# encoder.net
KiCad netlist of a schematic drawn in EAGLE
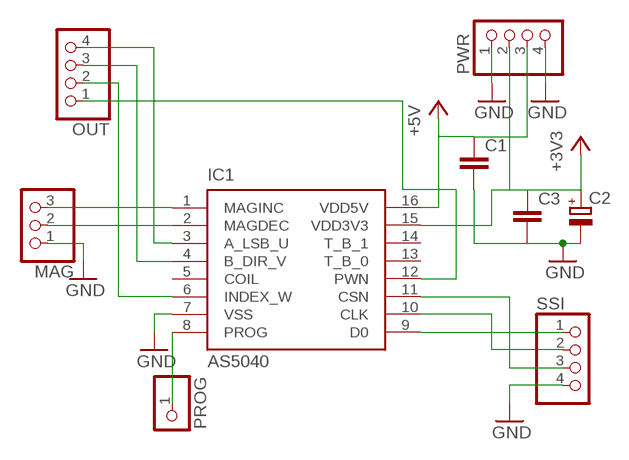
[diagram p0: schematic, sheet 1]

(export (version "E")
  (design (tool "Eeschema 10.0.6"))
  (components
    (comp (ref "C1")
      (value "C-EUC0805")
      (footprint "eagle-import:C0805")
      (libsource (lib "eagle-import") (part "C-EUC0805"))
    )
    (comp (ref "C2")
      (value "CPOL-EUE2,5-6E")
      (footprint "eagle-import:E2,5-6E")
      (libsource (lib "eagle-import") (part "CPOL-EUE2,5-6E"))
    )
    (comp (ref "C3")
      (value "C-EUC0805")
      (footprint "eagle-import:C0805")
      (libsource (lib "eagle-import") (part "C-EUC0805"))
    )
    (comp (ref "IC1")
      (value "AS5040")
      (footprint "eagle-import:SSOP16")
      (fields (field (name "MPN") "AS5040ASSU"))
      (libsource (lib "eagle-import") (part "AS5040"))
    )
    (comp (ref "MAG")
      (value "PINHD-1X3")
      (footprint "eagle-import:1X03")
      (libsource (lib "eagle-import") (part "PINHD-1X3"))
    )
    (comp (ref "OUT")
      (value "PINHD-1X4")
      (footprint "eagle-import:1X04")
      (libsource (lib "eagle-import") (part "PINHD-1X4"))
    )
    (comp (ref "PROG")
      (value "PINHD-1X1")
      (footprint "eagle-import:1X01")
      (libsource (lib "eagle-import") (part "PINHD-1X1"))
    )
    (comp (ref "PWR")
      (value "PINHD-1X4")
      (footprint "eagle-import:1X04")
      (libsource (lib "eagle-import") (part "PINHD-1X4"))
    )
    (comp (ref "SSI")
      (value "PINHD-1X4")
      (footprint "eagle-import:1X04")
      (libsource (lib "eagle-import") (part "PINHD-1X4"))
    )
  )
  (nets
    (net (code "1") (name "+3V3") (class "Default")
      (node (ref "C2") (pin "+") (pinfunction "+_+") (pintype "passive"))
      (node (ref "C3") (pin "1") (pinfunction "1_1") (pintype "passive"))
      (node (ref "IC1") (pin "15") (pinfunction "VDD3V3_15") (pintype "passive"))
      (node (ref "PWR") (pin "2") (pinfunction "2_2") (pintype "passive"))
    )
    (net (code "2") (name "+5V") (class "Default")
      (node (ref "C1") (pin "1") (pinfunction "1_1") (pintype "passive"))
      (node (ref "IC1") (pin "16") (pinfunction "VDD5V_16") (pintype "passive"))
      (node (ref "PWR") (pin "3") (pinfunction "3_3") (pintype "passive"))
    )
    (net (code "3") (name "GND") (class "Default")
      (node (ref "C1") (pin "2") (pinfunction "2_2") (pintype "passive"))
      (node (ref "C2") (pin "-") (pinfunction "-_-") (pintype "passive"))
      (node (ref "C3") (pin "2") (pinfunction "2_2") (pintype "passive"))
      (node (ref "IC1") (pin "7") (pinfunction "VSS_7") (pintype "passive"))
      (node (ref "MAG") (pin "1") (pinfunction "1_1") (pintype "passive"))
      (node (ref "PWR") (pin "1") (pinfunction "1_1") (pintype "passive"))
      (node (ref "PWR") (pin "4") (pinfunction "4_4") (pintype "passive"))
      (node (ref "SSI") (pin "4") (pinfunction "4_4") (pintype "passive"))
    )
    (net (code "4") (name "Net-(IC1-A_LSB_U)") (class "Default")
      (node (ref "IC1") (pin "3") (pinfunction "A_LSB_U_3") (pintype "output"))
      (node (ref "OUT") (pin "4") (pinfunction "4_4") (pintype "passive"))
    )
    (net (code "5") (name "Net-(IC1-B_DIR_V)") (class "Default")
      (node (ref "IC1") (pin "4") (pinfunction "B_DIR_V_4") (pintype "output"))
      (node (ref "OUT") (pin "3") (pinfunction "3_3") (pintype "passive"))
    )
    (net (code "6") (name "Net-(IC1-CLK)") (class "Default")
      (node (ref "IC1") (pin "10") (pinfunction "CLK_10") (pintype "input"))
      (node (ref "SSI") (pin "2") (pinfunction "2_2") (pintype "passive"))
    )
    (net (code "7") (name "Net-(IC1-CSN)") (class "Default")
      (node (ref "IC1") (pin "11") (pinfunction "CSN_11") (pintype "input"))
      (node (ref "SSI") (pin "3") (pinfunction "3_3") (pintype "passive"))
    )
    (net (code "8") (name "Net-(IC1-D0)") (class "Default")
      (node (ref "IC1") (pin "9") (pinfunction "D0_9") (pintype "tri_state"))
      (node (ref "SSI") (pin "1") (pinfunction "1_1") (pintype "passive"))
    )
    (net (code "9") (name "Net-(IC1-INDEX_W)") (class "Default")
      (node (ref "IC1") (pin "6") (pinfunction "INDEX_W_6") (pintype "output"))
      (node (ref "OUT") (pin "2") (pinfunction "2_2") (pintype "passive"))
    )
    (net (code "10") (name "Net-(IC1-MAGDEC)") (class "Default")
      (node (ref "IC1") (pin "2") (pinfunction "MAGDEC_2") (pintype "tri_state"))
      (node (ref "MAG") (pin "2") (pinfunction "2_2") (pintype "passive"))
    )
    (net (code "11") (name "Net-(IC1-MAGINC)") (class "Default")
      (node (ref "IC1") (pin "1") (pinfunction "MAGINC_1") (pintype "tri_state"))
      (node (ref "MAG") (pin "3") (pinfunction "3_3") (pintype "passive"))
    )
    (net (code "12") (name "Net-(IC1-PROG)") (class "Default")
      (node (ref "IC1") (pin "8") (pinfunction "PROG_8") (pintype "input"))
      (node (ref "PROG") (pin "1") (pinfunction "1_1") (pintype "passive"))
    )
    (net (code "13") (name "Net-(IC1-PWN)") (class "Default")
      (node (ref "IC1") (pin "12") (pinfunction "PWN_12") (pintype "passive"))
      (node (ref "OUT") (pin "1") (pinfunction "1_1") (pintype "passive"))
    )
    (net (code "14") (name "unconnected-(IC1-COIL-Pad5)") (class "Default")
      (node (ref "IC1") (pin "5") (pinfunction "COIL_5") (pintype "no_connect"))
    )
    (net (code "15") (name "unconnected-(IC1-T_B_0-Pad13)") (class "Default")
      (node (ref "IC1") (pin "13") (pinfunction "T_B_0_13") (pintype "no_connect"))
    )
    (net (code "16") (name "unconnected-(IC1-T_B_1-Pad14)") (class "Default")
      (node (ref "IC1") (pin "14") (pinfunction "T_B_1_14") (pintype "no_connect"))
    )
  )
)
